# SparkFun_Dev_ESP32_C3_PTH.net
KiCad netlist of a schematic drawn in EAGLE
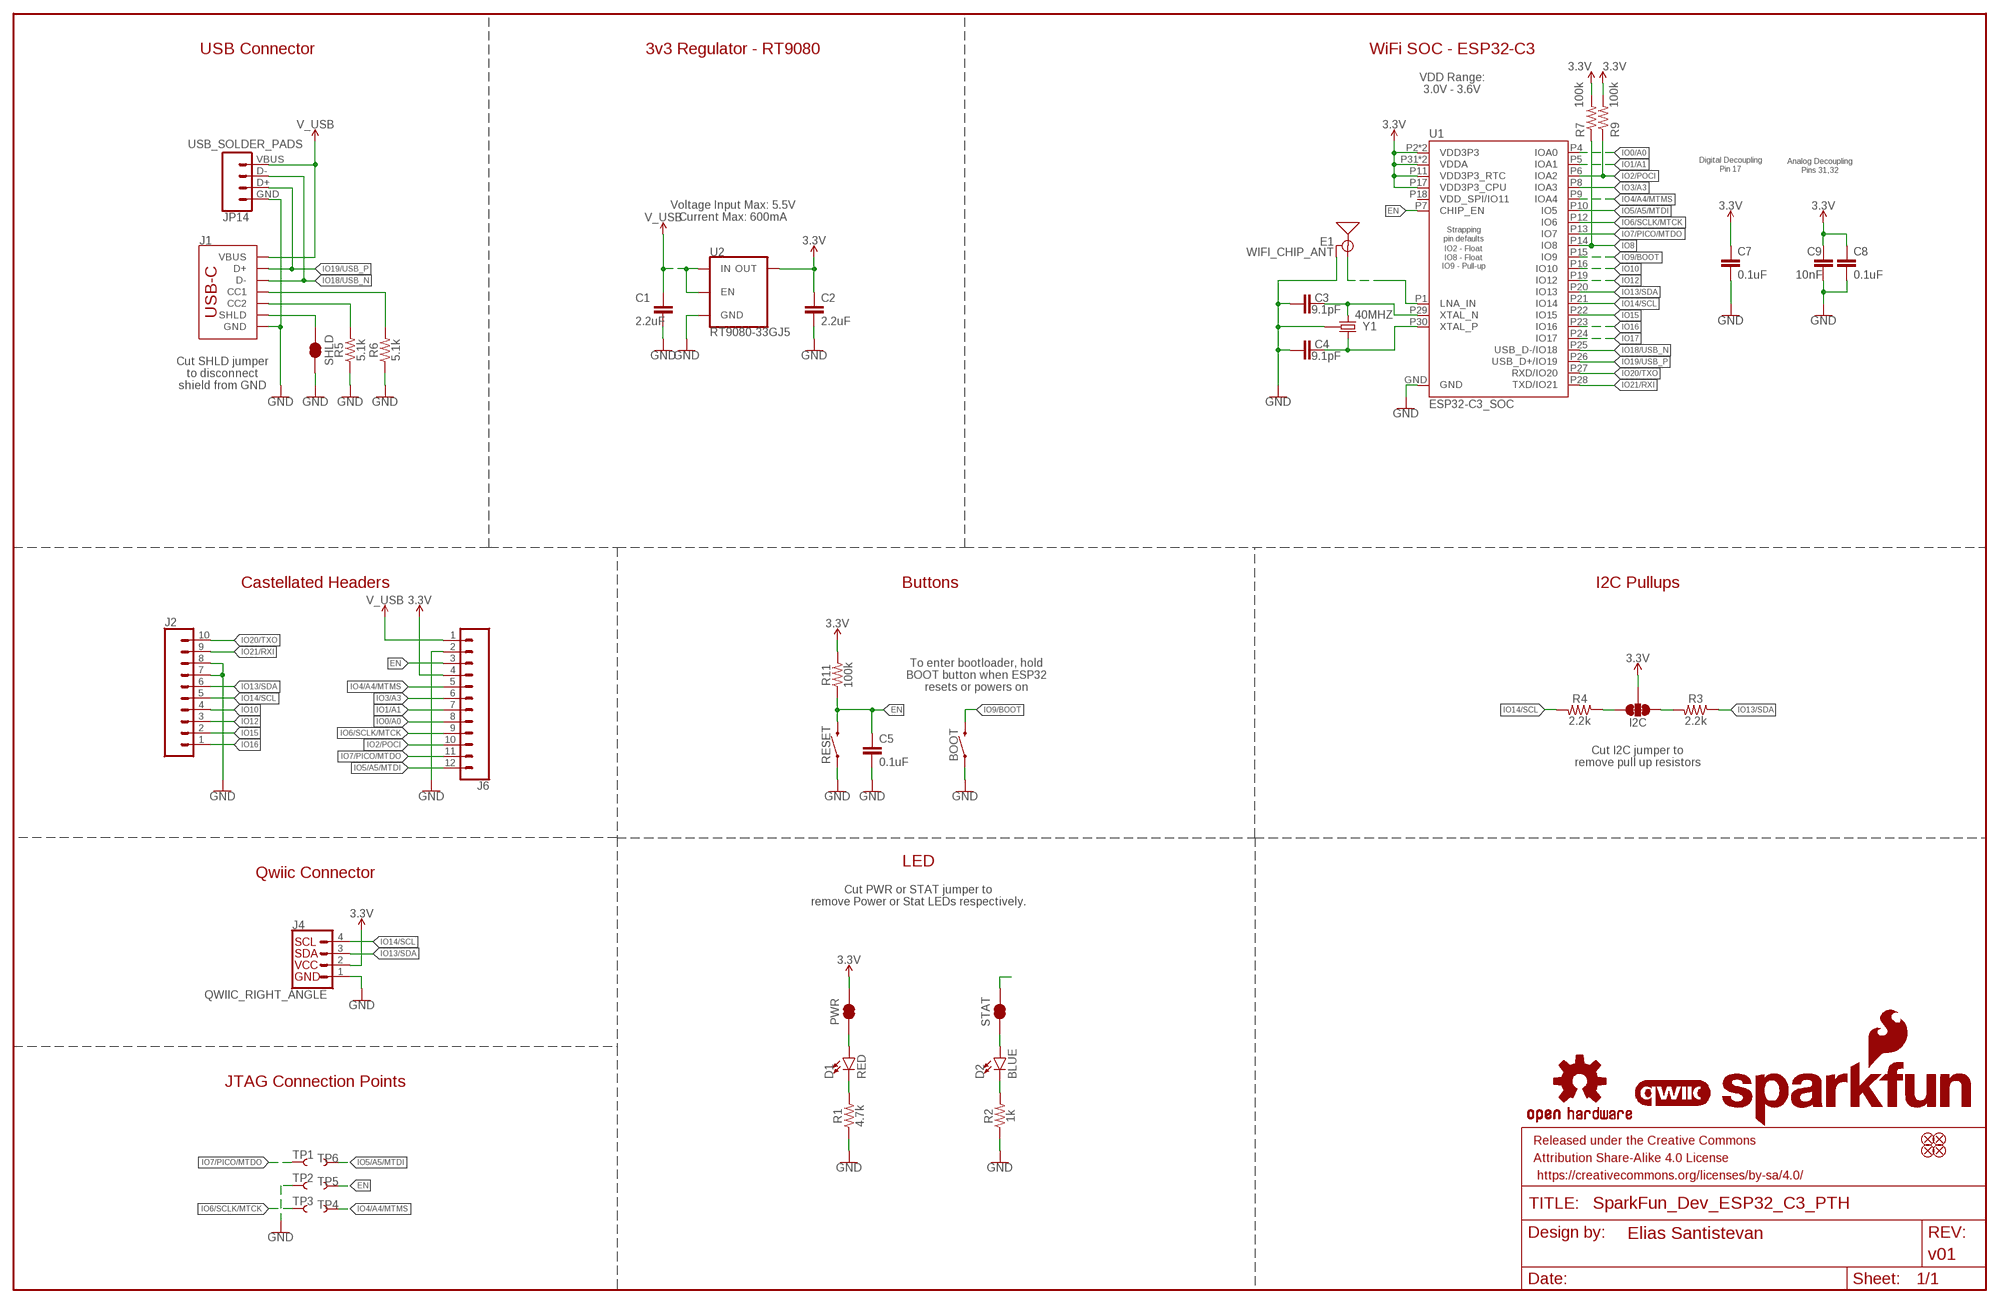
[diagram p0: schematic, sheet 1]

(export (version "E")
  (design (tool "Eeschema 10.0.6"))
  (components
    (comp (ref "BOOT")
      (value "MOMENTARY-SWITCH-SPST-SMD-4.6X2.8MM")
      (footprint "eagle-import:TACTILE_SWITCH_SMD_4.6X2.8MM")
      (libsource (lib "eagle-import") (part "MOMENTARY-SWITCH-SPST-SMD-4.6X2.8MM"))
    )
    (comp (ref "C1")
      (value "2.2uF")
      (footprint "eagle-import:0402-TIGHT")
      (libsource (lib "eagle-import") (part "2.2UF-0402_TIGHT-10V-10%-X5R"))
    )
    (comp (ref "C2")
      (value "2.2uF")
      (footprint "eagle-import:0402-TIGHT")
      (libsource (lib "eagle-import") (part "2.2UF-0402_TIGHT-10V-10%-X5R"))
    )
    (comp (ref "C3")
      (value "9.1pF")
      (footprint "eagle-import:0402-TIGHT")
      (fields (field (name "MOUSER_PART") "609-500R07S9R1CV4T"))
      (libsource (lib "eagle-import") (part "9.1PF-0402-TIGHT"))
    )
    (comp (ref "C4")
      (value "9.1pF")
      (footprint "eagle-import:0402-TIGHT")
      (fields (field (name "MOUSER_PART") "609-500R07S9R1CV4T"))
      (libsource (lib "eagle-import") (part "9.1PF-0402-TIGHT"))
    )
    (comp (ref "C5")
      (value "0.1uF")
      (footprint "eagle-import:0402-TIGHT")
      (libsource (lib "eagle-import") (part "0.1UF-0402T-6.3V-10%-X7R"))
    )
    (comp (ref "C7")
      (value "0.1uF")
      (footprint "eagle-import:0402-TIGHT")
      (libsource (lib "eagle-import") (part "0.1UF-0402T-16V-10%"))
    )
    (comp (ref "C8")
      (value "0.1uF")
      (footprint "eagle-import:0402-TIGHT")
      (libsource (lib "eagle-import") (part "0.1UF-0402T-16V-10%"))
    )
    (comp (ref "C9")
      (value "10nF")
      (footprint "eagle-import:0402-TIGHT")
      (libsource (lib "eagle-import") (part "10NF-0402T-25V-10%"))
    )
    (comp (ref "D1")
      (value "RED")
      (footprint "eagle-import:LED-0603")
      (libsource (lib "eagle-import") (part "LED-RED_0603-KB"))
    )
    (comp (ref "D2")
      (value "BLUE")
      (footprint "eagle-import:LED-0603")
      (libsource (lib "eagle-import") (part "LED-BLUE0603"))
    )
    (comp (ref "E1")
      (value "WIFI_CHIP_ANT")
      (footprint "eagle-import:CHIP_ANT_NO_COURTYARD")
      (libsource (lib "eagle-import") (part "WIFI_CHIP_ANT"))
    )
    (comp (ref "FD1")
      (value "FIDUCIALUFIDUCIAL")
      (footprint "eagle-import:FIDUCIAL-MICRO")
      (libsource (lib "eagle-import") (part "FIDUCIALUFIDUCIAL"))
    )
    (comp (ref "FD2")
      (value "FIDUCIALUFIDUCIAL")
      (footprint "eagle-import:FIDUCIAL-MICRO")
      (libsource (lib "eagle-import") (part "FIDUCIALUFIDUCIAL"))
    )
    (comp (ref "FD3")
      (value "FIDUCIALUFIDUCIAL")
      (footprint "eagle-import:FIDUCIAL-MICRO")
      (libsource (lib "eagle-import") (part "FIDUCIALUFIDUCIAL"))
    )
    (comp (ref "FD4")
      (value "FIDUCIALUFIDUCIAL")
      (footprint "eagle-import:FIDUCIAL-MICRO")
      (libsource (lib "eagle-import") (part "FIDUCIALUFIDUCIAL"))
    )
    (comp (ref "FRAME2")
      (value "FRAME-LEDGER")
      (footprint "eagle-import:CREATIVE_COMMONS")
      (fields (field (name "DESIGNER") "Elias Santistevan") (field (name "REV") "v01"))
      (libsource (lib "eagle-import") (part "FRAME-LEDGER"))
    )
    (comp (ref "I2C")
      (value "JUMPER-SMT_3_2-NC_TRACE_SILK")
      (footprint "eagle-import:SMT-JUMPER_3_2-NC_TRACE_SILK")
      (libsource (lib "eagle-import") (part "JUMPER-SMT_3_2-NC_TRACE_SILK"))
    )
    (comp (ref "J1")
      (value "USB Female Type C Connector")
      (footprint "eagle-import:USB-C-16P_4LAYER-PADS")
      (libsource (lib "eagle-import") (part "USB_C_4-LAYER_PADS"))
    )
    (comp (ref "J2")
      (value "CONN_10NO_SILK_PTH_FEMALE")
      (footprint "eagle-import:1X10_NO_SILK")
      (libsource (lib "eagle-import") (part "CONN_10NO_SILK_PTH_FEMALE"))
    )
    (comp (ref "J4")
      (value "QWIIC_RIGHT_ANGLE")
      (footprint "eagle-import:JST04_1MM_RA")
      (libsource (lib "eagle-import") (part "QWIIC_CONNECTORJS-1MM"))
    )
    (comp (ref "J6")
      (value "CONN_121X12_NO_SILK_KIT")
      (footprint "eagle-import:1X12_NO_SILK_KIT")
      (libsource (lib "eagle-import") (part "CONN_121X12_NO_SILK_KIT"))
    )
    (comp (ref "JP14")
      (value "USB_SOLDER_PADS")
      (footprint "eagle-import:USB-SOLDER-PADS")
      (libsource (lib "eagle-import") (part "USB_SOLDER_PADS"))
    )
    (comp (ref "LOGO1")
      (value "SFE_LOGO_NAME_FLAMEBLANK")
      (footprint "eagle-import:BLANK")
      (libsource (lib "eagle-import") (part "SFE_LOGO_NAME_FLAMEBLANK"))
    )
    (comp (ref "LOGO2")
      (value "QWIIC_LOGO_3MM")
      (footprint "eagle-import:QWIIC_3MM")
      (libsource (lib "eagle-import") (part "QWIIC_LOGO_3MM"))
    )
    (comp (ref "LOGO3")
      (value "OSHW-LOGOS")
      (footprint "eagle-import:OSHW-LOGO-S")
      (libsource (lib "eagle-import") (part "OSHW-LOGOS"))
    )
    (comp (ref "PWR")
      (value "JUMPER-SMT_2_NC_TRACE_SILK")
      (footprint "eagle-import:SMT-JUMPER_2_NC_TRACE_SILK")
      (libsource (lib "eagle-import") (part "JUMPER-SMT_2_NC_TRACE_SILK"))
    )
    (comp (ref "R1")
      (value "4.7k")
      (footprint "eagle-import:0402-TIGHT")
      (libsource (lib "eagle-import") (part "4.7KOHM-0402T-1/16W-1%"))
    )
    (comp (ref "R2")
      (value "1k")
      (footprint "eagle-import:0402-TIGHT")
      (libsource (lib "eagle-import") (part "1KOHM-0402T-1/16W-1%"))
    )
    (comp (ref "R3")
      (value "2.2k")
      (footprint "eagle-import:0402-TIGHT")
      (libsource (lib "eagle-import") (part "2.2KOHM-0402T-1/16W-1%"))
    )
    (comp (ref "R4")
      (value "2.2k")
      (footprint "eagle-import:0402-TIGHT")
      (libsource (lib "eagle-import") (part "2.2KOHM-0402T-1/16W-1%"))
    )
    (comp (ref "R5")
      (value "5.1k")
      (footprint "eagle-import:0402-TIGHT")
      (libsource (lib "eagle-import") (part "5.1KOHM-0402T-1/16W-1%"))
    )
    (comp (ref "R6")
      (value "5.1k")
      (footprint "eagle-import:0402-TIGHT")
      (libsource (lib "eagle-import") (part "5.1KOHM-0402T-1/16W-1%"))
    )
    (comp (ref "R7")
      (value "100k")
      (footprint "eagle-import:0402-TIGHT")
      (libsource (lib "eagle-import") (part "100KOHM-0402T-1/16W-1%"))
    )
    (comp (ref "R9")
      (value "100k")
      (footprint "eagle-import:0402-TIGHT")
      (libsource (lib "eagle-import") (part "100KOHM-0402T-1/16W-1%"))
    )
    (comp (ref "R11")
      (value "100k")
      (footprint "eagle-import:0402-TIGHT")
      (libsource (lib "eagle-import") (part "100KOHM-0402T-1/16W-1%"))
    )
    (comp (ref "RESET")
      (value "MOMENTARY-SWITCH-SPST-SMD-4.6X2.8MM")
      (footprint "eagle-import:TACTILE_SWITCH_SMD_4.6X2.8MM")
      (libsource (lib "eagle-import") (part "MOMENTARY-SWITCH-SPST-SMD-4.6X2.8MM"))
    )
    (comp (ref "SHLD")
      (value "JUMPER-SMT_2_NC_TRACE_SILK")
      (footprint "eagle-import:SMT-JUMPER_2_NC_TRACE_SILK")
      (libsource (lib "eagle-import") (part "JUMPER-SMT_2_NC_TRACE_SILK"))
    )
    (comp (ref "STAT")
      (value "JUMPER-SMT_2_NC_TRACE_SILK")
      (footprint "eagle-import:SMT-JUMPER_2_NC_TRACE_SILK")
      (libsource (lib "eagle-import") (part "JUMPER-SMT_2_NC_TRACE_SILK"))
    )
    (comp (ref "TP1")
      (value "TEST-POINT3X5")
      (footprint "eagle-import:PAD.03X.05")
      (libsource (lib "eagle-import") (part "TEST-POINT3X5"))
    )
    (comp (ref "TP2")
      (value "TEST-POINT3X5")
      (footprint "eagle-import:PAD.03X.05")
      (libsource (lib "eagle-import") (part "TEST-POINT3X5"))
    )
    (comp (ref "TP3")
      (value "TEST-POINT3X5")
      (footprint "eagle-import:PAD.03X.05")
      (libsource (lib "eagle-import") (part "TEST-POINT3X5"))
    )
    (comp (ref "TP4")
      (value "TEST-POINT3X5")
      (footprint "eagle-import:PAD.03X.05")
      (libsource (lib "eagle-import") (part "TEST-POINT3X5"))
    )
    (comp (ref "TP5")
      (value "TEST-POINT3X5")
      (footprint "eagle-import:PAD.03X.05")
      (libsource (lib "eagle-import") (part "TEST-POINT3X5"))
    )
    (comp (ref "TP6")
      (value "TEST-POINT3X5")
      (footprint "eagle-import:PAD.03X.05")
      (libsource (lib "eagle-import") (part "TEST-POINT3X5"))
    )
    (comp (ref "U1")
      (value "ESP32-C3_SOC")
      (footprint "eagle-import:QFN32")
      (libsource (lib "eagle-import") (part "ESP32-C3_SOC"))
    )
    (comp (ref "U2")
      (value "RT9080-33GJ5")
      (footprint "eagle-import:SOT23-5")
      (libsource (lib "eagle-import") (part "V_REG_RT9080"))
    )
    (comp (ref "Y1")
      (value "40MHZ")
      (footprint "eagle-import:CRYSTAL-SMD-2X2.5MM")
      (libsource (lib "eagle-import") (part "CRYSTAL-40MHZ-SMD-2X2.5MM"))
    )
  )
  (nets
    (net (code "1") (name "3.3V") (class "Default")
      (node (ref "C2") (pin "1") (pinfunction "1_1") (pintype "passive"))
      (node (ref "C7") (pin "1") (pinfunction "1_1") (pintype "passive"))
      (node (ref "C8") (pin "1") (pinfunction "1_1") (pintype "passive"))
      (node (ref "C9") (pin "1") (pinfunction "1_1") (pintype "passive"))
      (node (ref "I2C") (pin "2") (pinfunction "2_2") (pintype "passive"))
      (node (ref "J4") (pin "2") (pinfunction "2_2") (pintype "power_in"))
      (node (ref "J6") (pin "4") (pinfunction "4_4") (pintype "passive"))
      (node (ref "PWR") (pin "2") (pinfunction "2_2") (pintype "passive"))
      (node (ref "R11") (pin "2") (pinfunction "2_2") (pintype "passive"))
      (node (ref "R7") (pin "2") (pinfunction "2_2") (pintype "passive"))
      (node (ref "R9") (pin "2") (pinfunction "2_2") (pintype "passive"))
      (node (ref "U1") (pin "P11") (pinfunction "VDD3P3_RTC_P11") (pintype "bidirectional"))
      (node (ref "U1") (pin "P17") (pinfunction "VDD3P3_CPU_P17") (pintype "bidirectional"))
      (node (ref "U1") (pin "P2") (pinfunction "VDD3P3_P2") (pintype "bidirectional"))
      (node (ref "U1") (pin "P3") (pinfunction "VDD3P3_P3") (pintype "bidirectional"))
      (node (ref "U1") (pin "P31") (pinfunction "VDDA_P31") (pintype "bidirectional"))
      (node (ref "U1") (pin "P32") (pinfunction "VDDA_P32") (pintype "bidirectional"))
      (node (ref "U2") (pin "5") (pinfunction "OUT_5") (pintype "passive"))
    )
    (net (code "2") (name "EN") (class "Default")
      (node (ref "C5") (pin "1") (pinfunction "1_1") (pintype "passive"))
      (node (ref "J6") (pin "3") (pinfunction "3_3") (pintype "passive"))
      (node (ref "R11") (pin "1") (pinfunction "1_1") (pintype "passive"))
      (node (ref "RESET") (pin "3") (pinfunction "2_3") (pintype "passive"))
      (node (ref "RESET") (pin "4") (pinfunction "2_4") (pintype "passive"))
      (node (ref "TP5") (pin "1") (pinfunction "1_1") (pintype "bidirectional"))
      (node (ref "U1") (pin "P7") (pinfunction "CHIP_EN_P7") (pintype "bidirectional"))
    )
    (net (code "3") (name "GND") (class "Default")
      (node (ref "BOOT") (pin "1") (pinfunction "1_1") (pintype "passive"))
      (node (ref "BOOT") (pin "2") (pinfunction "1_2") (pintype "passive"))
      (node (ref "C1") (pin "2") (pinfunction "2_2") (pintype "passive"))
      (node (ref "C2") (pin "2") (pinfunction "2_2") (pintype "passive"))
      (node (ref "C3") (pin "1") (pinfunction "1_1") (pintype "passive"))
      (node (ref "C4") (pin "1") (pinfunction "1_1") (pintype "passive"))
      (node (ref "C5") (pin "2") (pinfunction "2_2") (pintype "passive"))
      (node (ref "C7") (pin "2") (pinfunction "2_2") (pintype "passive"))
      (node (ref "C8") (pin "2") (pinfunction "2_2") (pintype "passive"))
      (node (ref "C9") (pin "2") (pinfunction "2_2") (pintype "passive"))
      (node (ref "E1") (pin "P3") (pinfunction "GND_P3") (pintype "bidirectional"))
      (node (ref "E1") (pin "P4") (pinfunction "GND_P4") (pintype "bidirectional"))
      (node (ref "J1") (pin "GND") (pinfunction "GND_GND") (pintype "bidirectional"))
      (node (ref "J1") (pin "GND2") (pinfunction "GND_GND2") (pintype "bidirectional"))
      (node (ref "J2") (pin "7") (pinfunction "7_7") (pintype "passive"))
      (node (ref "J2") (pin "8") (pinfunction "8_8") (pintype "passive"))
      (node (ref "J4") (pin "1") (pinfunction "1_1") (pintype "power_in"))
      (node (ref "J6") (pin "2") (pinfunction "2_2") (pintype "passive"))
      (node (ref "JP14") (pin "GND") (pinfunction "4_GND") (pintype "passive"))
      (node (ref "R1") (pin "1") (pinfunction "1_1") (pintype "passive"))
      (node (ref "R2") (pin "1") (pinfunction "1_1") (pintype "passive"))
      (node (ref "R5") (pin "1") (pinfunction "1_1") (pintype "passive"))
      (node (ref "R6") (pin "1") (pinfunction "1_1") (pintype "passive"))
      (node (ref "RESET") (pin "1") (pinfunction "1_1") (pintype "passive"))
      (node (ref "RESET") (pin "2") (pinfunction "1_2") (pintype "passive"))
      (node (ref "SHLD") (pin "2") (pinfunction "2_2") (pintype "passive"))
      (node (ref "TP2") (pin "1") (pinfunction "1_1") (pintype "bidirectional"))
      (node (ref "U1") (pin "GND") (pinfunction "GND_GND") (pintype "bidirectional"))
      (node (ref "U2") (pin "2") (pinfunction "GND_2") (pintype "input"))
      (node (ref "Y1") (pin "P2") (pinfunction "GND_P2") (pintype "power_in"))
      (node (ref "Y1") (pin "P4") (pinfunction "GND_P4") (pintype "power_in"))
    )
    (net (code "4") (name "IO0{slash}A0") (class "Default")
      (node (ref "J6") (pin "8") (pinfunction "8_8") (pintype "passive"))
      (node (ref "U1") (pin "P4") (pinfunction "IOA0_P4") (pintype "bidirectional"))
    )
    (net (code "5") (name "IO1{slash}A1") (class "Default")
      (node (ref "J6") (pin "7") (pinfunction "7_7") (pintype "passive"))
      (node (ref "U1") (pin "P5") (pinfunction "IOA1_P5") (pintype "bidirectional"))
    )
    (net (code "6") (name "IO2{slash}POCI") (class "Default")
      (node (ref "J6") (pin "10") (pinfunction "10_10") (pintype "passive"))
      (node (ref "R9") (pin "1") (pinfunction "1_1") (pintype "passive"))
      (node (ref "U1") (pin "P6") (pinfunction "IOA2_P6") (pintype "bidirectional"))
    )
    (net (code "7") (name "IO3{slash}A3") (class "Default")
      (node (ref "J6") (pin "6") (pinfunction "6_6") (pintype "passive"))
      (node (ref "U1") (pin "P8") (pinfunction "IOA3_P8") (pintype "bidirectional"))
    )
    (net (code "8") (name "IO4{slash}A4{slash}MTMS") (class "Default")
      (node (ref "J6") (pin "5") (pinfunction "5_5") (pintype "passive"))
      (node (ref "TP4") (pin "1") (pinfunction "1_1") (pintype "bidirectional"))
      (node (ref "U1") (pin "P9") (pinfunction "IOA4_P9") (pintype "bidirectional"))
    )
    (net (code "9") (name "IO5{slash}A5{slash}MTDI") (class "Default")
      (node (ref "J6") (pin "12") (pinfunction "12_12") (pintype "passive"))
      (node (ref "TP6") (pin "1") (pinfunction "1_1") (pintype "bidirectional"))
      (node (ref "U1") (pin "P10") (pinfunction "IO5_P10") (pintype "bidirectional"))
    )
    (net (code "10") (name "IO6{slash}SCLK{slash}MTCK") (class "Default")
      (node (ref "J6") (pin "9") (pinfunction "9_9") (pintype "passive"))
      (node (ref "TP3") (pin "1") (pinfunction "1_1") (pintype "bidirectional"))
      (node (ref "U1") (pin "P12") (pinfunction "IO6_P12") (pintype "bidirectional"))
    )
    (net (code "11") (name "IO7{slash}PICO{slash}MTDO") (class "Default")
      (node (ref "J6") (pin "11") (pinfunction "11_11") (pintype "passive"))
      (node (ref "TP1") (pin "1") (pinfunction "1_1") (pintype "bidirectional"))
      (node (ref "U1") (pin "P13") (pinfunction "IO7_P13") (pintype "bidirectional"))
    )
    (net (code "12") (name "IO8") (class "Default")
      (node (ref "R7") (pin "1") (pinfunction "1_1") (pintype "passive"))
      (node (ref "U1") (pin "P14") (pinfunction "IO8_P14") (pintype "bidirectional"))
    )
    (net (code "13") (name "IO9{slash}BOOT") (class "Default")
      (node (ref "BOOT") (pin "3") (pinfunction "2_3") (pintype "passive"))
      (node (ref "BOOT") (pin "4") (pinfunction "2_4") (pintype "passive"))
      (node (ref "U1") (pin "P15") (pinfunction "IO9_P15") (pintype "bidirectional"))
    )
    (net (code "14") (name "IO10") (class "Default")
      (node (ref "J2") (pin "4") (pinfunction "4_4") (pintype "passive"))
      (node (ref "U1") (pin "P16") (pinfunction "IO10_P16") (pintype "bidirectional"))
    )
    (net (code "15") (name "IO12") (class "Default")
      (node (ref "J2") (pin "3") (pinfunction "3_3") (pintype "passive"))
      (node (ref "U1") (pin "P19") (pinfunction "IO12_P19") (pintype "bidirectional"))
    )
    (net (code "16") (name "IO13{slash}SDA") (class "Default")
      (node (ref "J2") (pin "6") (pinfunction "6_6") (pintype "passive"))
      (node (ref "J4") (pin "3") (pinfunction "3_3") (pintype "passive"))
      (node (ref "R3") (pin "1") (pinfunction "1_1") (pintype "passive"))
      (node (ref "U1") (pin "P20") (pinfunction "IO13_P20") (pintype "bidirectional"))
    )
    (net (code "17") (name "IO14{slash}SCL") (class "Default")
      (node (ref "J2") (pin "5") (pinfunction "5_5") (pintype "passive"))
      (node (ref "J4") (pin "4") (pinfunction "4_4") (pintype "passive"))
      (node (ref "R4") (pin "2") (pinfunction "2_2") (pintype "passive"))
      (node (ref "U1") (pin "P21") (pinfunction "IO14_P21") (pintype "bidirectional"))
    )
    (net (code "18") (name "IO15") (class "Default")
      (node (ref "J2") (pin "2") (pinfunction "2_2") (pintype "passive"))
      (node (ref "U1") (pin "P22") (pinfunction "IO15_P22") (pintype "bidirectional"))
    )
    (net (code "19") (name "IO16") (class "Default")
      (node (ref "J2") (pin "1") (pinfunction "1_1") (pintype "passive"))
      (node (ref "U1") (pin "P23") (pinfunction "IO16_P23") (pintype "bidirectional"))
    )
    (net (code "20") (name "IO17") (class "Default")
      (node (ref "U1") (pin "P24") (pinfunction "IO17_P24") (pintype "bidirectional"))
    )
    (net (code "21") (name "IO18{slash}USB_N") (class "Default")
      (node (ref "J1") (pin "A7") (pinfunction "D-_A7") (pintype "bidirectional"))
      (node (ref "J1") (pin "B7") (pinfunction "D-_B7") (pintype "bidirectional"))
      (node (ref "JP14") (pin "D-") (pinfunction "2_D-") (pintype "passive"))
      (node (ref "U1") (pin "P25") (pinfunction "USB_D-/IO18_P25") (pintype "bidirectional"))
    )
    (net (code "22") (name "IO19{slash}USB_P") (class "Default")
      (node (ref "J1") (pin "A6") (pinfunction "D+_A6") (pintype "bidirectional"))
      (node (ref "J1") (pin "B6") (pinfunction "D+_B6") (pintype "bidirectional"))
      (node (ref "JP14") (pin "D+") (pinfunction "3_D+") (pintype "passive"))
      (node (ref "U1") (pin "P26") (pinfunction "USB_D+/IO19_P26") (pintype "bidirectional"))
    )
    (net (code "23") (name "IO20{slash}TXO") (class "Default")
      (node (ref "J2") (pin "10") (pinfunction "10_10") (pintype "passive"))
      (node (ref "U1") (pin "P27") (pinfunction "RXD/IO20_P27") (pintype "bidirectional"))
    )
    (net (code "24") (name "IO21{slash}RXI") (class "Default")
      (node (ref "J2") (pin "9") (pinfunction "9_9") (pintype "passive"))
      (node (ref "U1") (pin "P28") (pinfunction "TXD/IO21_P28") (pintype "bidirectional"))
    )
    (net (code "25") (name "Net-(D1-PadA)") (class "Default")
      (node (ref "D1") (pin "A") (pinfunction "A_A") (pintype "passive"))
      (node (ref "PWR") (pin "1") (pinfunction "1_1") (pintype "passive"))
    )
    (net (code "26") (name "Net-(D1-PadC)") (class "Default")
      (node (ref "D1") (pin "C") (pinfunction "C_C") (pintype "passive"))
      (node (ref "R1") (pin "2") (pinfunction "2_2") (pintype "passive"))
    )
    (net (code "27") (name "Net-(D2-PadA)") (class "Default")
      (node (ref "D2") (pin "A") (pinfunction "A_A") (pintype "passive"))
      (node (ref "STAT") (pin "1") (pinfunction "1_1") (pintype "passive"))
    )
    (net (code "28") (name "Net-(D2-PadC)") (class "Default")
      (node (ref "D2") (pin "C") (pinfunction "C_C") (pintype "passive"))
      (node (ref "R2") (pin "2") (pinfunction "2_2") (pintype "passive"))
    )
    (net (code "29") (name "Net-(E1-SIGNAL)") (class "Default")
      (node (ref "E1") (pin "P1") (pinfunction "SIGNAL_P1") (pintype "bidirectional"))
      (node (ref "U1") (pin "P1") (pinfunction "LNA_IN_P1") (pintype "bidirectional"))
    )
    (net (code "30") (name "Net-(I2C-Pad1)") (class "Default")
      (node (ref "I2C") (pin "1") (pinfunction "1_1") (pintype "passive"))
      (node (ref "R4") (pin "1") (pinfunction "1_1") (pintype "passive"))
    )
    (net (code "31") (name "Net-(I2C-Pad3)") (class "Default")
      (node (ref "I2C") (pin "3") (pinfunction "3_3") (pintype "passive"))
      (node (ref "R3") (pin "2") (pinfunction "2_2") (pintype "passive"))
    )
    (net (code "32") (name "Net-(J1-CC1)") (class "Default")
      (node (ref "J1") (pin "A5") (pinfunction "CC1_A5") (pintype "bidirectional"))
      (node (ref "R6") (pin "2") (pinfunction "2_2") (pintype "passive"))
    )
    (net (code "33") (name "Net-(J1-CC2)") (class "Default")
      (node (ref "J1") (pin "B5") (pinfunction "CC2_B5") (pintype "bidirectional"))
      (node (ref "R5") (pin "2") (pinfunction "2_2") (pintype "passive"))
    )
    (net (code "34") (name "Net-(J1-SHLD-PadSHLD1)") (class "Default")
      (node (ref "J1") (pin "SHLD1") (pinfunction "SHLD_SHLD1") (pintype "bidirectional"))
      (node (ref "J1") (pin "SHLD2") (pinfunction "SHLD_SHLD2") (pintype "bidirectional"))
      (node (ref "J1") (pin "SHLD3") (pinfunction "SHLD_SHLD3") (pintype "bidirectional"))
      (node (ref "J1") (pin "SHLD4") (pinfunction "SHLD_SHLD4") (pintype "bidirectional"))
      (node (ref "SHLD") (pin "1") (pinfunction "1_1") (pintype "passive"))
    )
    (net (code "35") (name "Net-(U1-XTAL_N)") (class "Default")
      (node (ref "C3") (pin "2") (pinfunction "2_2") (pintype "passive"))
      (node (ref "U1") (pin "P29") (pinfunction "XTAL_N_P29") (pintype "bidirectional"))
      (node (ref "Y1") (pin "P1") (pinfunction "1_P1") (pintype "passive"))
    )
    (net (code "36") (name "Net-(U1-XTAL_P)") (class "Default")
      (node (ref "C4") (pin "2") (pinfunction "2_2") (pintype "passive"))
      (node (ref "U1") (pin "P30") (pinfunction "XTAL_P_P30") (pintype "bidirectional"))
      (node (ref "Y1") (pin "P3") (pinfunction "2_P3") (pintype "passive"))
    )
    (net (code "37") (name "V_USB") (class "Default")
      (node (ref "C1") (pin "1") (pinfunction "1_1") (pintype "passive"))
      (node (ref "J1") (pin "VBUS1") (pinfunction "VBUS_VBUS1") (pintype "bidirectional"))
      (node (ref "J1") (pin "VBUS2") (pinfunction "VBUS_VBUS2") (pintype "bidirectional"))
      (node (ref "J6") (pin "1") (pinfunction "1_1") (pintype "passive"))
      (node (ref "JP14") (pin "VBUS") (pinfunction "1_VBUS") (pintype "passive"))
      (node (ref "U2") (pin "1") (pinfunction "IN_1") (pintype "input"))
      (node (ref "U2") (pin "3") (pinfunction "EN_3") (pintype "input"))
    )
    (net (code "38") (name "unconnected-(STAT-Pad2)") (class "Default")
      (node (ref "STAT") (pin "2") (pinfunction "2_2") (pintype "passive"))
    )
    (net (code "39") (name "unconnected-(U1-VDD_SPI{slash}IO11-PadP18)") (class "Default")
      (node (ref "U1") (pin "P18") (pinfunction "VDD_SPI/IO11_P18") (pintype "bidirectional"))
    )
  )
)
